# Hub.net
KiCad netlist of a schematic drawn in Altium Designer
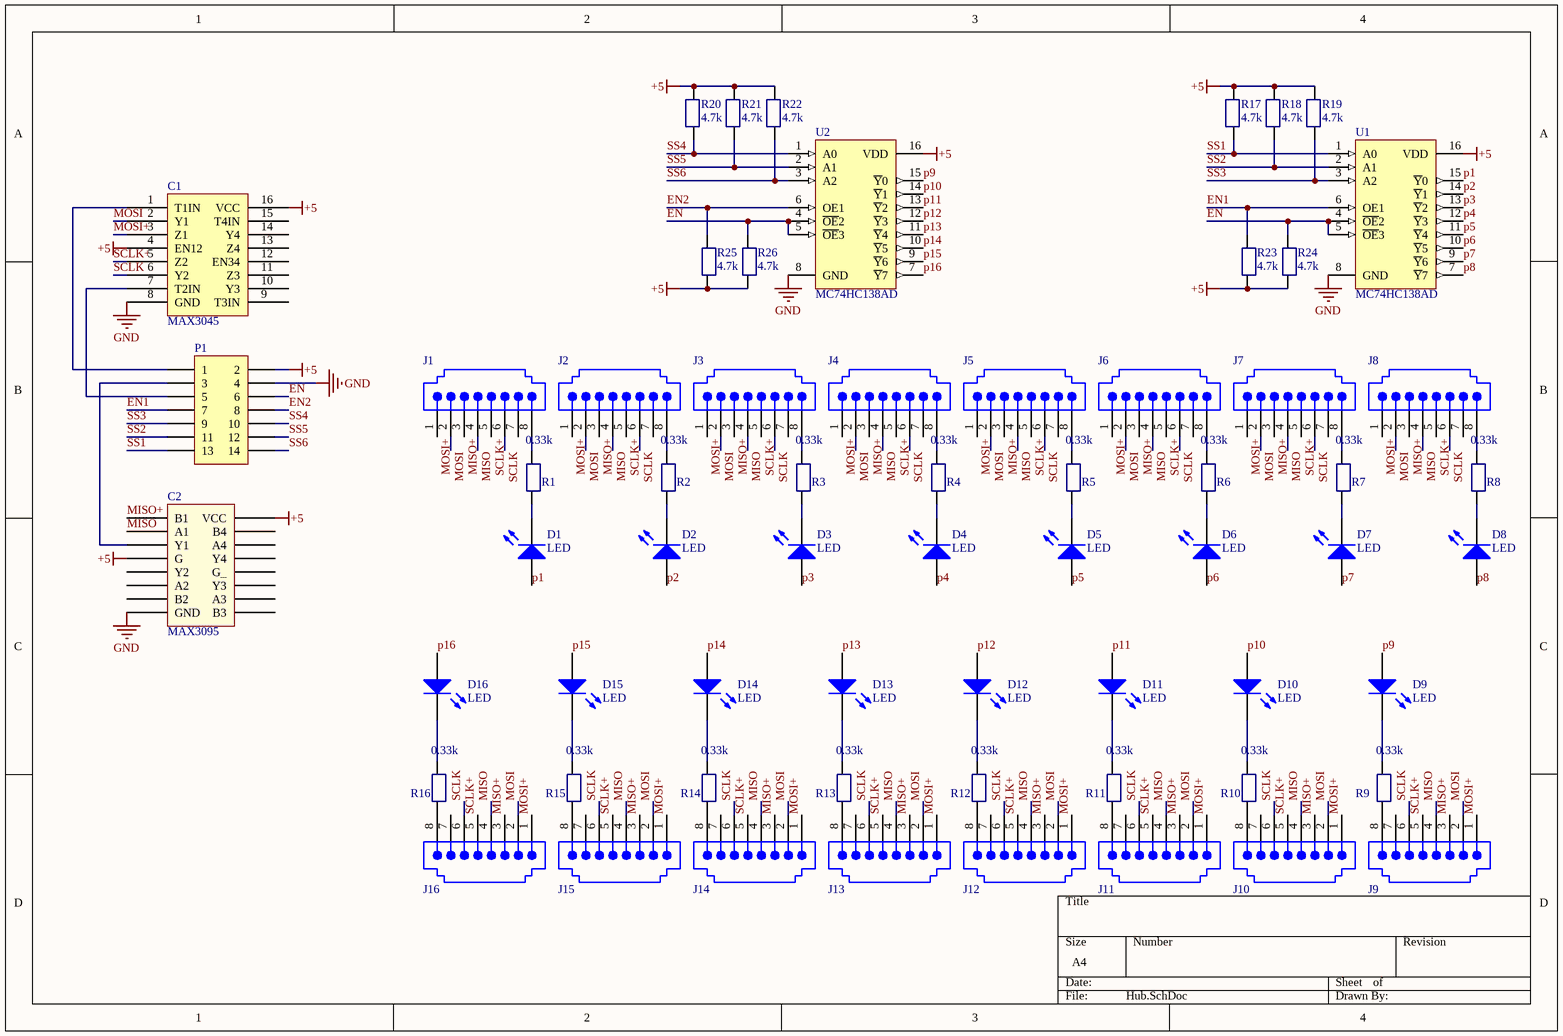
[diagram p0: Hub.SchDoc]

(export (version "E")
  (design (tool "Eeschema 10.0.6"))
  (components
    (comp (ref "C1") (value "MAX3045") (footprint "SOP16") (libsource (lib "DeersADLib") (part "MAX3045")))
    (comp (ref "C2") (value "MAX3095") (footprint "SOP16") (libsource (lib "DeersADLib") (part "MAX3095")))
    (comp (ref "D1")
      (value "LED")
      (footprint "3.5X2.8X1.9")
      (description "Typical BLUE SiC LED")
      (fields (field (name "PUBLISHER") "Altium Limited"))
      (libsource (lib "Miscellaneous Devices") (part "LED3"))
    )
    (comp (ref "D2")
      (value "LED")
      (footprint "3.5X2.8X1.9")
      (description "Typical BLUE SiC LED")
      (fields (field (name "PUBLISHER") "Altium Limited"))
      (libsource (lib "Miscellaneous Devices") (part "LED3"))
    )
    (comp (ref "D3")
      (value "LED")
      (footprint "3.5X2.8X1.9")
      (description "Typical BLUE SiC LED")
      (fields (field (name "PUBLISHER") "Altium Limited"))
      (libsource (lib "Miscellaneous Devices") (part "LED3"))
    )
    (comp (ref "D4")
      (value "LED")
      (footprint "3.5X2.8X1.9")
      (description "Typical BLUE SiC LED")
      (fields (field (name "PUBLISHER") "Altium Limited"))
      (libsource (lib "Miscellaneous Devices") (part "LED3"))
    )
    (comp (ref "D5")
      (value "LED")
      (footprint "3.5X2.8X1.9")
      (description "Typical BLUE SiC LED")
      (fields (field (name "PUBLISHER") "Altium Limited"))
      (libsource (lib "Miscellaneous Devices") (part "LED3"))
    )
    (comp (ref "D6")
      (value "LED")
      (footprint "3.5X2.8X1.9")
      (description "Typical BLUE SiC LED")
      (fields (field (name "PUBLISHER") "Altium Limited"))
      (libsource (lib "Miscellaneous Devices") (part "LED3"))
    )
    (comp (ref "D7")
      (value "LED")
      (footprint "3.5X2.8X1.9")
      (description "Typical BLUE SiC LED")
      (fields (field (name "PUBLISHER") "Altium Limited"))
      (libsource (lib "Miscellaneous Devices") (part "LED3"))
    )
    (comp (ref "D8")
      (value "LED")
      (footprint "3.5X2.8X1.9")
      (description "Typical BLUE SiC LED")
      (fields (field (name "PUBLISHER") "Altium Limited"))
      (libsource (lib "Miscellaneous Devices") (part "LED3"))
    )
    (comp (ref "D9")
      (value "LED")
      (footprint "3.5X2.8X1.9")
      (description "Typical BLUE SiC LED")
      (fields (field (name "PUBLISHER") "Altium Limited"))
      (libsource (lib "Miscellaneous Devices") (part "LED3"))
    )
    (comp (ref "D10")
      (value "LED")
      (footprint "3.5X2.8X1.9")
      (description "Typical BLUE SiC LED")
      (fields (field (name "PUBLISHER") "Altium Limited"))
      (libsource (lib "Miscellaneous Devices") (part "LED3"))
    )
    (comp (ref "D11")
      (value "LED")
      (footprint "3.5X2.8X1.9")
      (description "Typical BLUE SiC LED")
      (fields (field (name "PUBLISHER") "Altium Limited"))
      (libsource (lib "Miscellaneous Devices") (part "LED3"))
    )
    (comp (ref "D12")
      (value "LED")
      (footprint "3.5X2.8X1.9")
      (description "Typical BLUE SiC LED")
      (fields (field (name "PUBLISHER") "Altium Limited"))
      (libsource (lib "Miscellaneous Devices") (part "LED3"))
    )
    (comp (ref "D13")
      (value "LED")
      (footprint "3.5X2.8X1.9")
      (description "Typical BLUE SiC LED")
      (fields (field (name "PUBLISHER") "Altium Limited"))
      (libsource (lib "Miscellaneous Devices") (part "LED3"))
    )
    (comp (ref "D14")
      (value "LED")
      (footprint "3.5X2.8X1.9")
      (description "Typical BLUE SiC LED")
      (fields (field (name "PUBLISHER") "Altium Limited"))
      (libsource (lib "Miscellaneous Devices") (part "LED3"))
    )
    (comp (ref "D15")
      (value "LED")
      (footprint "3.5X2.8X1.9")
      (description "Typical BLUE SiC LED")
      (fields (field (name "PUBLISHER") "Altium Limited"))
      (libsource (lib "Miscellaneous Devices") (part "LED3"))
    )
    (comp (ref "D16")
      (value "LED")
      (footprint "3.5X2.8X1.9")
      (description "Typical BLUE SiC LED")
      (fields (field (name "PUBLISHER") "Altium Limited"))
      (libsource (lib "Miscellaneous Devices") (part "LED3"))
    )
    (comp (ref "J1")
      (value "15-43-6233")
      (footprint "15-43-6233")
      (description "Right Angle, Standard Profile, RJ45-Keyed, Flange Mount PCB Jack")
      (fields (field (name "PUBLISHER") "Altium Limited"))
      (libsource (lib "Molex Modular Jack Right Angle") (part "15-43-6233"))
    )
    (comp (ref "J2")
      (value "15-43-6233")
      (footprint "15-43-6233")
      (description "Right Angle, Standard Profile, RJ45-Keyed, Flange Mount PCB Jack")
      (fields (field (name "PUBLISHER") "Altium Limited"))
      (libsource (lib "Molex Modular Jack Right Angle") (part "15-43-6233"))
    )
    (comp (ref "J3")
      (value "15-43-6233")
      (footprint "15-43-6233")
      (description "Right Angle, Standard Profile, RJ45-Keyed, Flange Mount PCB Jack")
      (fields (field (name "PUBLISHER") "Altium Limited"))
      (libsource (lib "Molex Modular Jack Right Angle") (part "15-43-6233"))
    )
    (comp (ref "J4")
      (value "15-43-6233")
      (footprint "15-43-6233")
      (description "Right Angle, Standard Profile, RJ45-Keyed, Flange Mount PCB Jack")
      (fields (field (name "PUBLISHER") "Altium Limited"))
      (libsource (lib "Molex Modular Jack Right Angle") (part "15-43-6233"))
    )
    (comp (ref "J5")
      (value "15-43-6233")
      (footprint "15-43-6233")
      (description "Right Angle, Standard Profile, RJ45-Keyed, Flange Mount PCB Jack")
      (fields (field (name "PUBLISHER") "Altium Limited"))
      (libsource (lib "Molex Modular Jack Right Angle") (part "15-43-6233"))
    )
    (comp (ref "J6")
      (value "15-43-6233")
      (footprint "15-43-6233")
      (description "Right Angle, Standard Profile, RJ45-Keyed, Flange Mount PCB Jack")
      (fields (field (name "PUBLISHER") "Altium Limited"))
      (libsource (lib "Molex Modular Jack Right Angle") (part "15-43-6233"))
    )
    (comp (ref "J7")
      (value "15-43-6233")
      (footprint "15-43-6233")
      (description "Right Angle, Standard Profile, RJ45-Keyed, Flange Mount PCB Jack")
      (fields (field (name "PUBLISHER") "Altium Limited"))
      (libsource (lib "Molex Modular Jack Right Angle") (part "15-43-6233"))
    )
    (comp (ref "J8")
      (value "15-43-6233")
      (footprint "15-43-6233")
      (description "Right Angle, Standard Profile, RJ45-Keyed, Flange Mount PCB Jack")
      (fields (field (name "PUBLISHER") "Altium Limited"))
      (libsource (lib "Molex Modular Jack Right Angle") (part "15-43-6233"))
    )
    (comp (ref "J9")
      (value "15-43-6233")
      (footprint "15-43-6233")
      (description "Right Angle, Standard Profile, RJ45-Keyed, Flange Mount PCB Jack")
      (fields (field (name "PUBLISHER") "Altium Limited"))
      (libsource (lib "Molex Modular Jack Right Angle") (part "15-43-6233"))
    )
    (comp (ref "J10")
      (value "15-43-6233")
      (footprint "15-43-6233")
      (description "Right Angle, Standard Profile, RJ45-Keyed, Flange Mount PCB Jack")
      (fields (field (name "PUBLISHER") "Altium Limited"))
      (libsource (lib "Molex Modular Jack Right Angle") (part "15-43-6233"))
    )
    (comp (ref "J11")
      (value "15-43-6233")
      (footprint "15-43-6233")
      (description "Right Angle, Standard Profile, RJ45-Keyed, Flange Mount PCB Jack")
      (fields (field (name "PUBLISHER") "Altium Limited"))
      (libsource (lib "Molex Modular Jack Right Angle") (part "15-43-6233"))
    )
    (comp (ref "J12")
      (value "15-43-6233")
      (footprint "15-43-6233")
      (description "Right Angle, Standard Profile, RJ45-Keyed, Flange Mount PCB Jack")
      (fields (field (name "PUBLISHER") "Altium Limited"))
      (libsource (lib "Molex Modular Jack Right Angle") (part "15-43-6233"))
    )
    (comp (ref "J13")
      (value "15-43-6233")
      (footprint "15-43-6233")
      (description "Right Angle, Standard Profile, RJ45-Keyed, Flange Mount PCB Jack")
      (fields (field (name "PUBLISHER") "Altium Limited"))
      (libsource (lib "Molex Modular Jack Right Angle") (part "15-43-6233"))
    )
    (comp (ref "J14")
      (value "15-43-6233")
      (footprint "15-43-6233")
      (description "Right Angle, Standard Profile, RJ45-Keyed, Flange Mount PCB Jack")
      (fields (field (name "PUBLISHER") "Altium Limited"))
      (libsource (lib "Molex Modular Jack Right Angle") (part "15-43-6233"))
    )
    (comp (ref "J15")
      (value "15-43-6233")
      (footprint "15-43-6233")
      (description "Right Angle, Standard Profile, RJ45-Keyed, Flange Mount PCB Jack")
      (fields (field (name "PUBLISHER") "Altium Limited"))
      (libsource (lib "Molex Modular Jack Right Angle") (part "15-43-6233"))
    )
    (comp (ref "J16")
      (value "15-43-6233")
      (footprint "15-43-6233")
      (description "Right Angle, Standard Profile, RJ45-Keyed, Flange Mount PCB Jack")
      (fields (field (name "PUBLISHER") "Altium Limited"))
      (libsource (lib "Molex Modular Jack Right Angle") (part "15-43-6233"))
    )
    (comp (ref "P1")
      (value "Header 7X2")
      (footprint "HDR1X14")
      (description "Header, 7-Pin, Dual row")
      (fields (field (name "PUBLISHER") "Altium Limited"))
      (libsource (lib "Common Headers") (part "Header 7X2"))
    )
    (comp (ref "R1")
      (value "0.33k")
      (footprint "R0805")
      (libsource (lib "Common Device") (part "Resistance"))
    )
    (comp (ref "R2")
      (value "0.33k")
      (footprint "R0805")
      (libsource (lib "Common Device") (part "Resistance"))
    )
    (comp (ref "R3")
      (value "0.33k")
      (footprint "R0805")
      (libsource (lib "Common Device") (part "Resistance"))
    )
    (comp (ref "R4")
      (value "0.33k")
      (footprint "R0805")
      (libsource (lib "Common Device") (part "Resistance"))
    )
    (comp (ref "R5")
      (value "0.33k")
      (footprint "R0805")
      (libsource (lib "Common Device") (part "Resistance"))
    )
    (comp (ref "R6")
      (value "0.33k")
      (footprint "R0805")
      (libsource (lib "Common Device") (part "Resistance"))
    )
    (comp (ref "R7")
      (value "0.33k")
      (footprint "R0805")
      (libsource (lib "Common Device") (part "Resistance"))
    )
    (comp (ref "R8")
      (value "0.33k")
      (footprint "R0805")
      (libsource (lib "Common Device") (part "Resistance"))
    )
    (comp (ref "R9")
      (value "0.33k")
      (footprint "R0805")
      (libsource (lib "Common Device") (part "Resistance"))
    )
    (comp (ref "R10")
      (value "0.33k")
      (footprint "R0805")
      (libsource (lib "Common Device") (part "Resistance"))
    )
    (comp (ref "R11")
      (value "0.33k")
      (footprint "R0805")
      (libsource (lib "Common Device") (part "Resistance"))
    )
    (comp (ref "R12")
      (value "0.33k")
      (footprint "R0805")
      (libsource (lib "Common Device") (part "Resistance"))
    )
    (comp (ref "R13")
      (value "0.33k")
      (footprint "R0805")
      (libsource (lib "Common Device") (part "Resistance"))
    )
    (comp (ref "R14")
      (value "0.33k")
      (footprint "R0805")
      (libsource (lib "Common Device") (part "Resistance"))
    )
    (comp (ref "R15")
      (value "0.33k")
      (footprint "R0805")
      (libsource (lib "Common Device") (part "Resistance"))
    )
    (comp (ref "R16")
      (value "0.33k")
      (footprint "R0805")
      (libsource (lib "Common Device") (part "Resistance"))
    )
    (comp (ref "R17")
      (value "4.7k")
      (footprint "R0805")
      (libsource (lib "Common Device") (part "Resistance"))
    )
    (comp (ref "R18")
      (value "4.7k")
      (footprint "R0805")
      (libsource (lib "Common Device") (part "Resistance"))
    )
    (comp (ref "R19")
      (value "4.7k")
      (footprint "R0805")
      (libsource (lib "Common Device") (part "Resistance"))
    )
    (comp (ref "R20")
      (value "4.7k")
      (footprint "R0805")
      (libsource (lib "Common Device") (part "Resistance"))
    )
    (comp (ref "R21")
      (value "4.7k")
      (footprint "R0805")
      (libsource (lib "Common Device") (part "Resistance"))
    )
    (comp (ref "R22")
      (value "4.7k")
      (footprint "R0805")
      (libsource (lib "Common Device") (part "Resistance"))
    )
    (comp (ref "R23")
      (value "4.7k")
      (footprint "R0805")
      (libsource (lib "Common Device") (part "Resistance"))
    )
    (comp (ref "R24")
      (value "4.7k")
      (footprint "R0805")
      (libsource (lib "Common Device") (part "Resistance"))
    )
    (comp (ref "R25")
      (value "4.7k")
      (footprint "R0805")
      (libsource (lib "Common Device") (part "Resistance"))
    )
    (comp (ref "R26")
      (value "4.7k")
      (footprint "R0805")
      (libsource (lib "Common Device") (part "Resistance"))
    )
    (comp (ref "U1")
      (value "MC74HC138AD")
      (footprint "751B-03_L")
      (description "1-of-8 Decoder/Demultiplexer")
      (fields (field (name "PUBLISHER") "Altium Limited"))
      (libsource (lib "Motorola Logic Decoder Demux") (part "MC74HC138AD"))
    )
    (comp (ref "U2")
      (value "MC74HC138AD")
      (footprint "751B-03_L")
      (description "1-of-8 Decoder/Demultiplexer")
      (fields (field (name "PUBLISHER") "Altium Limited"))
      (libsource (lib "Motorola Logic Decoder Demux") (part "MC74HC138AD"))
    )
  )
  (nets
    (net (code "1") (name "+5") (class "Default")
      (node (ref "C1") (pin "16") (pinfunction "VCC_16") (pintype "passive"))
      (node (ref "C1") (pin "4") (pinfunction "EN12_4") (pintype "passive"))
      (node (ref "C2") (pin "16") (pinfunction "VCC_16") (pintype "passive"))
      (node (ref "C2") (pin "4") (pinfunction "G_4") (pintype "passive"))
      (node (ref "P1") (pin "2") (pinfunction "2_2") (pintype "passive"))
      (node (ref "R17") (pin "1") (pintype "passive"))
      (node (ref "R18") (pin "1") (pintype "passive"))
      (node (ref "R19") (pin "1") (pintype "passive"))
      (node (ref "R20") (pin "1") (pintype "passive"))
      (node (ref "R21") (pin "1") (pintype "passive"))
      (node (ref "R22") (pin "1") (pintype "passive"))
      (node (ref "R23") (pin "1") (pintype "passive"))
      (node (ref "R24") (pin "1") (pintype "passive"))
      (node (ref "R25") (pin "1") (pintype "passive"))
      (node (ref "R26") (pin "1") (pintype "passive"))
      (node (ref "U1") (pin "16") (pinfunction "VDD_16") (pintype "power_in"))
      (node (ref "U2") (pin "16") (pinfunction "VDD_16") (pintype "power_in"))
    )
    (net (code "2") (name "/EN") (class "Default")
      (node (ref "P1") (pin "6") (pinfunction "6_6") (pintype "passive"))
      (node (ref "R24") (pin "2") (pintype "passive"))
      (node (ref "R26") (pin "2") (pintype "passive"))
      (node (ref "U1") (pin "4") (pinfunction "~{OE}2_4") (pintype "input"))
      (node (ref "U1") (pin "5") (pinfunction "~{OE}3_5") (pintype "input"))
      (node (ref "U2") (pin "4") (pinfunction "~{OE}2_4") (pintype "input"))
      (node (ref "U2") (pin "5") (pinfunction "~{OE}3_5") (pintype "input"))
    )
    (net (code "3") (name "/EN1") (class "Default")
      (node (ref "P1") (pin "7") (pinfunction "7_7") (pintype "passive"))
      (node (ref "R23") (pin "2") (pintype "passive"))
      (node (ref "U1") (pin "6") (pinfunction "OE1_6") (pintype "input"))
    )
    (net (code "4") (name "/EN2") (class "Default")
      (node (ref "P1") (pin "8") (pinfunction "8_8") (pintype "passive"))
      (node (ref "R25") (pin "2") (pintype "passive"))
      (node (ref "U2") (pin "6") (pinfunction "OE1_6") (pintype "input"))
    )
    (net (code "5") (name "/MISO") (class "Default")
      (node (ref "C2") (pin "2") (pinfunction "A1_2") (pintype "passive"))
      (node (ref "J1") (pin "4") (pinfunction "4_4") (pintype "passive"))
      (node (ref "J10") (pin "4") (pinfunction "4_4") (pintype "passive"))
      (node (ref "J11") (pin "4") (pinfunction "4_4") (pintype "passive"))
      (node (ref "J12") (pin "4") (pinfunction "4_4") (pintype "passive"))
      (node (ref "J13") (pin "4") (pinfunction "4_4") (pintype "passive"))
      (node (ref "J14") (pin "4") (pinfunction "4_4") (pintype "passive"))
      (node (ref "J15") (pin "4") (pinfunction "4_4") (pintype "passive"))
      (node (ref "J16") (pin "4") (pinfunction "4_4") (pintype "passive"))
      (node (ref "J2") (pin "4") (pinfunction "4_4") (pintype "passive"))
      (node (ref "J3") (pin "4") (pinfunction "4_4") (pintype "passive"))
      (node (ref "J4") (pin "4") (pinfunction "4_4") (pintype "passive"))
      (node (ref "J5") (pin "4") (pinfunction "4_4") (pintype "passive"))
      (node (ref "J6") (pin "4") (pinfunction "4_4") (pintype "passive"))
      (node (ref "J7") (pin "4") (pinfunction "4_4") (pintype "passive"))
      (node (ref "J8") (pin "4") (pinfunction "4_4") (pintype "passive"))
      (node (ref "J9") (pin "4") (pinfunction "4_4") (pintype "passive"))
    )
    (net (code "6") (name "/MISO+") (class "Default")
      (node (ref "C2") (pin "1") (pinfunction "B1_1") (pintype "passive"))
      (node (ref "J1") (pin "3") (pinfunction "3_3") (pintype "passive"))
      (node (ref "J10") (pin "3") (pinfunction "3_3") (pintype "passive"))
      (node (ref "J11") (pin "3") (pinfunction "3_3") (pintype "passive"))
      (node (ref "J12") (pin "3") (pinfunction "3_3") (pintype "passive"))
      (node (ref "J13") (pin "3") (pinfunction "3_3") (pintype "passive"))
      (node (ref "J14") (pin "3") (pinfunction "3_3") (pintype "passive"))
      (node (ref "J15") (pin "3") (pinfunction "3_3") (pintype "passive"))
      (node (ref "J16") (pin "3") (pinfunction "3_3") (pintype "passive"))
      (node (ref "J2") (pin "3") (pinfunction "3_3") (pintype "passive"))
      (node (ref "J3") (pin "3") (pinfunction "3_3") (pintype "passive"))
      (node (ref "J4") (pin "3") (pinfunction "3_3") (pintype "passive"))
      (node (ref "J5") (pin "3") (pinfunction "3_3") (pintype "passive"))
      (node (ref "J6") (pin "3") (pinfunction "3_3") (pintype "passive"))
      (node (ref "J7") (pin "3") (pinfunction "3_3") (pintype "passive"))
      (node (ref "J8") (pin "3") (pinfunction "3_3") (pintype "passive"))
      (node (ref "J9") (pin "3") (pinfunction "3_3") (pintype "passive"))
    )
    (net (code "7") (name "/MOSI") (class "Default")
      (node (ref "C1") (pin "2") (pinfunction "Y1_2") (pintype "passive"))
      (node (ref "J1") (pin "2") (pinfunction "2_2") (pintype "passive"))
      (node (ref "J10") (pin "2") (pinfunction "2_2") (pintype "passive"))
      (node (ref "J11") (pin "2") (pinfunction "2_2") (pintype "passive"))
      (node (ref "J12") (pin "2") (pinfunction "2_2") (pintype "passive"))
      (node (ref "J13") (pin "2") (pinfunction "2_2") (pintype "passive"))
      (node (ref "J14") (pin "2") (pinfunction "2_2") (pintype "passive"))
      (node (ref "J15") (pin "2") (pinfunction "2_2") (pintype "passive"))
      (node (ref "J16") (pin "2") (pinfunction "2_2") (pintype "passive"))
      (node (ref "J2") (pin "2") (pinfunction "2_2") (pintype "passive"))
      (node (ref "J3") (pin "2") (pinfunction "2_2") (pintype "passive"))
      (node (ref "J4") (pin "2") (pinfunction "2_2") (pintype "passive"))
      (node (ref "J5") (pin "2") (pinfunction "2_2") (pintype "passive"))
      (node (ref "J6") (pin "2") (pinfunction "2_2") (pintype "passive"))
      (node (ref "J7") (pin "2") (pinfunction "2_2") (pintype "passive"))
      (node (ref "J8") (pin "2") (pinfunction "2_2") (pintype "passive"))
      (node (ref "J9") (pin "2") (pinfunction "2_2") (pintype "passive"))
    )
    (net (code "8") (name "/MOSI+") (class "Default")
      (node (ref "C1") (pin "3") (pinfunction "Z1_3") (pintype "passive"))
      (node (ref "J1") (pin "1") (pinfunction "1_1") (pintype "passive"))
      (node (ref "J10") (pin "1") (pinfunction "1_1") (pintype "passive"))
      (node (ref "J11") (pin "1") (pinfunction "1_1") (pintype "passive"))
      (node (ref "J12") (pin "1") (pinfunction "1_1") (pintype "passive"))
      (node (ref "J13") (pin "1") (pinfunction "1_1") (pintype "passive"))
      (node (ref "J14") (pin "1") (pinfunction "1_1") (pintype "passive"))
      (node (ref "J15") (pin "1") (pinfunction "1_1") (pintype "passive"))
      (node (ref "J16") (pin "1") (pinfunction "1_1") (pintype "passive"))
      (node (ref "J2") (pin "1") (pinfunction "1_1") (pintype "passive"))
      (node (ref "J3") (pin "1") (pinfunction "1_1") (pintype "passive"))
      (node (ref "J4") (pin "1") (pinfunction "1_1") (pintype "passive"))
      (node (ref "J5") (pin "1") (pinfunction "1_1") (pintype "passive"))
      (node (ref "J6") (pin "1") (pinfunction "1_1") (pintype "passive"))
      (node (ref "J7") (pin "1") (pinfunction "1_1") (pintype "passive"))
      (node (ref "J8") (pin "1") (pinfunction "1_1") (pintype "passive"))
      (node (ref "J9") (pin "1") (pinfunction "1_1") (pintype "passive"))
    )
    (net (code "9") (name "/SCLK") (class "Default")
      (node (ref "C1") (pin "6") (pinfunction "Y2_6") (pintype "passive"))
      (node (ref "J1") (pin "6") (pinfunction "6_6") (pintype "passive"))
      (node (ref "J10") (pin "6") (pinfunction "6_6") (pintype "passive"))
      (node (ref "J11") (pin "6") (pinfunction "6_6") (pintype "passive"))
      (node (ref "J12") (pin "6") (pinfunction "6_6") (pintype "passive"))
      (node (ref "J13") (pin "6") (pinfunction "6_6") (pintype "passive"))
      (node (ref "J14") (pin "6") (pinfunction "6_6") (pintype "passive"))
      (node (ref "J15") (pin "6") (pinfunction "6_6") (pintype "passive"))
      (node (ref "J16") (pin "6") (pinfunction "6_6") (pintype "passive"))
      (node (ref "J2") (pin "6") (pinfunction "6_6") (pintype "passive"))
      (node (ref "J3") (pin "6") (pinfunction "6_6") (pintype "passive"))
      (node (ref "J4") (pin "6") (pinfunction "6_6") (pintype "passive"))
      (node (ref "J5") (pin "6") (pinfunction "6_6") (pintype "passive"))
      (node (ref "J6") (pin "6") (pinfunction "6_6") (pintype "passive"))
      (node (ref "J7") (pin "6") (pinfunction "6_6") (pintype "passive"))
      (node (ref "J8") (pin "6") (pinfunction "6_6") (pintype "passive"))
      (node (ref "J9") (pin "6") (pinfunction "6_6") (pintype "passive"))
    )
    (net (code "10") (name "/SCLK+") (class "Default")
      (node (ref "C1") (pin "5") (pinfunction "Z2_5") (pintype "passive"))
      (node (ref "J1") (pin "5") (pinfunction "5_5") (pintype "passive"))
      (node (ref "J10") (pin "5") (pinfunction "5_5") (pintype "passive"))
      (node (ref "J11") (pin "5") (pinfunction "5_5") (pintype "passive"))
      (node (ref "J12") (pin "5") (pinfunction "5_5") (pintype "passive"))
      (node (ref "J13") (pin "5") (pinfunction "5_5") (pintype "passive"))
      (node (ref "J14") (pin "5") (pinfunction "5_5") (pintype "passive"))
      (node (ref "J15") (pin "5") (pinfunction "5_5") (pintype "passive"))
      (node (ref "J16") (pin "5") (pinfunction "5_5") (pintype "passive"))
      (node (ref "J2") (pin "5") (pinfunction "5_5") (pintype "passive"))
      (node (ref "J3") (pin "5") (pinfunction "5_5") (pintype "passive"))
      (node (ref "J4") (pin "5") (pinfunction "5_5") (pintype "passive"))
      (node (ref "J5") (pin "5") (pinfunction "5_5") (pintype "passive"))
      (node (ref "J6") (pin "5") (pinfunction "5_5") (pintype "passive"))
      (node (ref "J7") (pin "5") (pinfunction "5_5") (pintype "passive"))
      (node (ref "J8") (pin "5") (pinfunction "5_5") (pintype "passive"))
      (node (ref "J9") (pin "5") (pinfunction "5_5") (pintype "passive"))
    )
    (net (code "11") (name "/SS1") (class "Default")
      (node (ref "P1") (pin "13") (pinfunction "13_13") (pintype "passive"))
      (node (ref "R17") (pin "2") (pintype "passive"))
      (node (ref "U1") (pin "1") (pinfunction "A0_1") (pintype "input"))
    )
    (net (code "12") (name "/SS2") (class "Default")
      (node (ref "P1") (pin "11") (pinfunction "11_11") (pintype "passive"))
      (node (ref "R18") (pin "2") (pintype "passive"))
      (node (ref "U1") (pin "2") (pinfunction "A1_2") (pintype "input"))
    )
    (net (code "13") (name "/SS3") (class "Default")
      (node (ref "P1") (pin "9") (pinfunction "9_9") (pintype "passive"))
      (node (ref "R19") (pin "2") (pintype "passive"))
      (node (ref "U1") (pin "3") (pinfunction "A2_3") (pintype "input"))
    )
    (net (code "14") (name "/SS4") (class "Default")
      (node (ref "P1") (pin "10") (pinfunction "10_10") (pintype "passive"))
      (node (ref "R20") (pin "2") (pintype "passive"))
      (node (ref "U2") (pin "1") (pinfunction "A0_1") (pintype "input"))
    )
    (net (code "15") (name "/SS5") (class "Default")
      (node (ref "P1") (pin "12") (pinfunction "12_12") (pintype "passive"))
      (node (ref "R21") (pin "2") (pintype "passive"))
      (node (ref "U2") (pin "2") (pinfunction "A1_2") (pintype "input"))
    )
    (net (code "16") (name "/SS6") (class "Default")
      (node (ref "P1") (pin "14") (pinfunction "14_14") (pintype "passive"))
      (node (ref "R22") (pin "2") (pintype "passive"))
      (node (ref "U2") (pin "3") (pinfunction "A2_3") (pintype "input"))
    )
    (net (code "17") (name "/p1") (class "Default")
      (node (ref "D1") (pin "1") (pinfunction "A_1") (pintype "passive"))
      (node (ref "U1") (pin "15") (pinfunction "~{Y}0_15") (pintype "output"))
    )
    (net (code "18") (name "/p2") (class "Default")
      (node (ref "D2") (pin "1") (pinfunction "A_1") (pintype "passive"))
      (node (ref "U1") (pin "14") (pinfunction "~{Y}1_14") (pintype "output"))
    )
    (net (code "19") (name "/p3") (class "Default")
      (node (ref "D3") (pin "1") (pinfunction "A_1") (pintype "passive"))
      (node (ref "U1") (pin "13") (pinfunction "~{Y}2_13") (pintype "output"))
    )
    (net (code "20") (name "/p4") (class "Default")
      (node (ref "D4") (pin "1") (pinfunction "A_1") (pintype "passive"))
      (node (ref "U1") (pin "12") (pinfunction "~{Y}3_12") (pintype "output"))
    )
    (net (code "21") (name "/p5") (class "Default")
      (node (ref "D5") (pin "1") (pinfunction "A_1") (pintype "passive"))
      (node (ref "U1") (pin "11") (pinfunction "~{Y}4_11") (pintype "output"))
    )
    (net (code "22") (name "/p6") (class "Default")
      (node (ref "D6") (pin "1") (pinfunction "A_1") (pintype "passive"))
      (node (ref "U1") (pin "10") (pinfunction "~{Y}5_10") (pintype "output"))
    )
    (net (code "23") (name "/p7") (class "Default")
      (node (ref "D7") (pin "1") (pinfunction "A_1") (pintype "passive"))
      (node (ref "U1") (pin "9") (pinfunction "~{Y}6_9") (pintype "output"))
    )
    (net (code "24") (name "/p8") (class "Default")
      (node (ref "D8") (pin "1") (pinfunction "A_1") (pintype "passive"))
      (node (ref "U1") (pin "7") (pinfunction "~{Y}7_7") (pintype "output"))
    )
    (net (code "25") (name "/p9") (class "Default")
      (node (ref "D9") (pin "1") (pinfunction "A_1") (pintype "passive"))
      (node (ref "U2") (pin "15") (pinfunction "~{Y}0_15") (pintype "output"))
    )
    (net (code "26") (name "/p10") (class "Default")
      (node (ref "D10") (pin "1") (pinfunction "A_1") (pintype "passive"))
      (node (ref "U2") (pin "14") (pinfunction "~{Y}1_14") (pintype "output"))
    )
    (net (code "27") (name "/p11") (class "Default")
      (node (ref "D11") (pin "1") (pinfunction "A_1") (pintype "passive"))
      (node (ref "U2") (pin "13") (pinfunction "~{Y}2_13") (pintype "output"))
    )
    (net (code "28") (name "/p12") (class "Default")
      (node (ref "D12") (pin "1") (pinfunction "A_1") (pintype "passive"))
      (node (ref "U2") (pin "12") (pinfunction "~{Y}3_12") (pintype "output"))
    )
    (net (code "29") (name "/p13") (class "Default")
      (node (ref "D13") (pin "1") (pinfunction "A_1") (pintype "passive"))
      (node (ref "U2") (pin "11") (pinfunction "~{Y}4_11") (pintype "output"))
    )
    (net (code "30") (name "/p14") (class "Default")
      (node (ref "D14") (pin "1") (pinfunction "A_1") (pintype "passive"))
      (node (ref "U2") (pin "10") (pinfunction "~{Y}5_10") (pintype "output"))
    )
    (net (code "31") (name "/p15") (class "Default")
      (node (ref "D15") (pin "1") (pinfunction "A_1") (pintype "passive"))
      (node (ref "U2") (pin "9") (pinfunction "~{Y}6_9") (pintype "output"))
    )
    (net (code "32") (name "/p16") (class "Default")
      (node (ref "D16") (pin "1") (pinfunction "A_1") (pintype "passive"))
      (node (ref "U2") (pin "7") (pinfunction "~{Y}7_7") (pintype "output"))
    )
    (net (code "33") (name "GND") (class "Default")
      (node (ref "C1") (pin "8") (pinfunction "GND_8") (pintype "passive"))
      (node (ref "C2") (pin "8") (pinfunction "GND_8") (pintype "passive"))
      (node (ref "P1") (pin "4") (pinfunction "4_4") (pintype "passive"))
      (node (ref "U1") (pin "8") (pinfunction "GND_8") (pintype "power_in"))
      (node (ref "U2") (pin "8") (pinfunction "GND_8") (pintype "power_in"))
    )
    (net (code "34") (name "Net-(C1-T1IN)") (class "Default")
      (node (ref "C1") (pin "1") (pinfunction "T1IN_1") (pintype "passive"))
      (node (ref "P1") (pin "1") (pinfunction "1_1") (pintype "passive"))
    )
    (net (code "35") (name "Net-(C1-T2IN)") (class "Default")
      (node (ref "C1") (pin "7") (pinfunction "T2IN_7") (pintype "passive"))
      (node (ref "P1") (pin "5") (pinfunction "5_5") (pintype "passive"))
    )
    (net (code "36") (name "Net-(C2-Y1)") (class "Default")
      (node (ref "C2") (pin "3") (pinfunction "Y1_3") (pintype "passive"))
      (node (ref "P1") (pin "3") (pinfunction "3_3") (pintype "passive"))
    )
    (net (code "37") (name "Net-(D1-K)") (class "Default")
      (node (ref "D1") (pin "2") (pinfunction "K_2") (pintype "passive"))
      (node (ref "R1") (pin "1") (pintype "passive"))
    )
    (net (code "38") (name "Net-(D2-K)") (class "Default")
      (node (ref "D2") (pin "2") (pinfunction "K_2") (pintype "passive"))
      (node (ref "R2") (pin "1") (pintype "passive"))
    )
    (net (code "39") (name "Net-(D3-K)") (class "Default")
      (node (ref "D3") (pin "2") (pinfunction "K_2") (pintype "passive"))
      (node (ref "R3") (pin "1") (pintype "passive"))
    )
    (net (code "40") (name "Net-(D4-K)") (class "Default")
      (node (ref "D4") (pin "2") (pinfunction "K_2") (pintype "passive"))
      (node (ref "R4") (pin "1") (pintype "passive"))
    )
    (net (code "41") (name "Net-(D5-K)") (class "Default")
      (node (ref "D5") (pin "2") (pinfunction "K_2") (pintype "passive"))
      (node (ref "R5") (pin "1") (pintype "passive"))
    )
    (net (code "42") (name "Net-(D6-K)") (class "Default")
      (node (ref "D6") (pin "2") (pinfunction "K_2") (pintype "passive"))
      (node (ref "R6") (pin "1") (pintype "passive"))
    )
    (net (code "43") (name "Net-(D7-K)") (class "Default")
      (node (ref "D7") (pin "2") (pinfunction "K_2") (pintype "passive"))
      (node (ref "R7") (pin "1") (pintype "passive"))
    )
    (net (code "44") (name "Net-(D8-K)") (class "Default")
      (node (ref "D8") (pin "2") (pinfunction "K_2") (pintype "passive"))
      (node (ref "R8") (pin "1") (pintype "passive"))
    )
    (net (code "45") (name "Net-(D9-K)") (class "Default")
      (node (ref "D9") (pin "2") (pinfunction "K_2") (pintype "passive"))
      (node (ref "R9") (pin "2") (pintype "passive"))
    )
    (net (code "46") (name "Net-(D10-K)") (class "Default")
      (node (ref "D10") (pin "2") (pinfunction "K_2") (pintype "passive"))
      (node (ref "R10") (pin "2") (pintype "passive"))
    )
    (net (code "47") (name "Net-(D11-K)") (class "Default")
      (node (ref "D11") (pin "2") (pinfunction "K_2") (pintype "passive"))
      (node (ref "R11") (pin "2") (pintype "passive"))
    )
    (net (code "48") (name "Net-(D12-K)") (class "Default")
      (node (ref "D12") (pin "2") (pinfunction "K_2") (pintype "passive"))
      (node (ref "R12") (pin "2") (pintype "passive"))
    )
    (net (code "49") (name "Net-(D13-K)") (class "Default")
      (node (ref "D13") (pin "2") (pinfunction "K_2") (pintype "passive"))
      (node (ref "R13") (pin "2") (pintype "passive"))
    )
    (net (code "50") (name "Net-(D14-K)") (class "Default")
      (node (ref "D14") (pin "2") (pinfunction "K_2") (pintype "passive"))
      (node (ref "R14") (pin "2") (pintype "passive"))
    )
    (net (code "51") (name "Net-(D15-K)") (class "Default")
      (node (ref "D15") (pin "2") (pinfunction "K_2") (pintype "passive"))
      (node (ref "R15") (pin "2") (pintype "passive"))
    )
    (net (code "52") (name "Net-(D16-K)") (class "Default")
      (node (ref "D16") (pin "2") (pinfunction "K_2") (pintype "passive"))
      (node (ref "R16") (pin "2") (pintype "passive"))
    )
    (net (code "53") (name "Net-(J1-Pad8)") (class "Default")
      (node (ref "J1") (pin "8") (pinfunction "8_8") (pintype "passive"))
      (node (ref "R1") (pin "2") (pintype "passive"))
    )
    (net (code "54") (name "Net-(J2-Pad8)") (class "Default")
      (node (ref "J2") (pin "8") (pinfunction "8_8") (pintype "passive"))
      (node (ref "R2") (pin "2") (pintype "passive"))
    )
    (net (code "55") (name "Net-(J3-Pad8)") (class "Default")
      (node (ref "J3") (pin "8") (pinfunction "8_8") (pintype "passive"))
      (node (ref "R3") (pin "2") (pintype "passive"))
    )
    (net (code "56") (name "Net-(J4-Pad8)") (class "Default")
      (node (ref "J4") (pin "8") (pinfunction "8_8") (pintype "passive"))
      (node (ref "R4") (pin "2") (pintype "passive"))
    )
    (net (code "57") (name "Net-(J5-Pad8)") (class "Default")
      (node (ref "J5") (pin "8") (pinfunction "8_8") (pintype "passive"))
      (node (ref "R5") (pin "2") (pintype "passive"))
    )
    (net (code "58") (name "Net-(J6-Pad8)") (class "Default")
      (node (ref "J6") (pin "8") (pinfunction "8_8") (pintype "passive"))
      (node (ref "R6") (pin "2") (pintype "passive"))
    )
    (net (code "59") (name "Net-(J7-Pad8)") (class "Default")
      (node (ref "J7") (pin "8") (pinfunction "8_8") (pintype "passive"))
      (node (ref "R7") (pin "2") (pintype "passive"))
    )
    (net (code "60") (name "Net-(J8-Pad8)") (class "Default")
      (node (ref "J8") (pin "8") (pinfunction "8_8") (pintype "passive"))
      (node (ref "R8") (pin "2") (pintype "passive"))
    )
    (net (code "61") (name "Net-(J9-Pad8)") (class "Default")
      (node (ref "J9") (pin "8") (pinfunction "8_8") (pintype "passive"))
      (node (ref "R9") (pin "1") (pintype "passive"))
    )
    (net (code "62") (name "Net-(J10-Pad8)") (class "Default")
      (node (ref "J10") (pin "8") (pinfunction "8_8") (pintype "passive"))
      (node (ref "R10") (pin "1") (pintype "passive"))
    )
    (net (code "63") (name "Net-(J11-Pad8)") (class "Default")
      (node (ref "J11") (pin "8") (pinfunction "8_8") (pintype "passive"))
      (node (ref "R11") (pin "1") (pintype "passive"))
    )
    (net (code "64") (name "Net-(J12-Pad8)") (class "Default")
      (node (ref "J12") (pin "8") (pinfunction "8_8") (pintype "passive"))
      (node (ref "R12") (pin "1") (pintype "passive"))
    )
    (net (code "65") (name "Net-(J13-Pad8)") (class "Default")
      (node (ref "J13") (pin "8") (pinfunction "8_8") (pintype "passive"))
      (node (ref "R13") (pin "1") (pintype "passive"))
    )
    (net (code "66") (name "Net-(J14-Pad8)") (class "Default")
      (node (ref "J14") (pin "8") (pinfunction "8_8") (pintype "passive"))
      (node (ref "R14") (pin "1") (pintype "passive"))
    )
    (net (code "67") (name "Net-(J15-Pad8)") (class "Default")
      (node (ref "J15") (pin "8") (pinfunction "8_8") (pintype "passive"))
      (node (ref "R15") (pin "1") (pintype "passive"))
    )
    (net (code "68") (name "Net-(J16-Pad8)") (class "Default")
      (node (ref "J16") (pin "8") (pinfunction "8_8") (pintype "passive"))
      (node (ref "R16") (pin "1") (pintype "passive"))
    )
    (net (code "69") (name "unconnected-(C1-EN34-Pad12)") (class "Default")
      (node (ref "C1") (pin "12") (pinfunction "EN34_12") (pintype "passive"))
    )
    (net (code "70") (name "unconnected-(C1-T3IN-Pad9)") (class "Default")
      (node (ref "C1") (pin "9") (pinfunction "T3IN_9") (pintype "passive"))
    )
    (net (code "71") (name "unconnected-(C1-T4IN-Pad15)") (class "Default")
      (node (ref "C1") (pin "15") (pinfunction "T4IN_15") (pintype "passive"))
    )
    (net (code "72") (name "unconnected-(C1-Y3-Pad10)") (class "Default")
      (node (ref "C1") (pin "10") (pinfunction "Y3_10") (pintype "passive"))
    )
    (net (code "73") (name "unconnected-(C1-Y4-Pad14)") (class "Default")
      (node (ref "C1") (pin "14") (pinfunction "Y4_14") (pintype "passive"))
    )
    (net (code "74") (name "unconnected-(C1-Z3-Pad11)") (class "Default")
      (node (ref "C1") (pin "11") (pinfunction "Z3_11") (pintype "passive"))
    )
    (net (code "75") (name "unconnected-(C1-Z4-Pad13)") (class "Default")
      (node (ref "C1") (pin "13") (pinfunction "Z4_13") (pintype "passive"))
    )
    (net (code "76") (name "unconnected-(C2-A2-Pad6)") (class "Default")
      (node (ref "C2") (pin "6") (pinfunction "A2_6") (pintype "passive"))
    )
    (net (code "77") (name "unconnected-(C2-A3-Pad10)") (class "Default")
      (node (ref "C2") (pin "10") (pinfunction "A3_10") (pintype "passive"))
    )
    (net (code "78") (name "unconnected-(C2-A4-Pad14)") (class "Default")
      (node (ref "C2") (pin "14") (pinfunction "A4_14") (pintype "passive"))
    )
    (net (code "79") (name "unconnected-(C2-B2-Pad7)") (class "Default")
      (node (ref "C2") (pin "7") (pinfunction "B2_7") (pintype "passive"))
    )
    (net (code "80") (name "unconnected-(C2-B3-Pad9)") (class "Default")
      (node (ref "C2") (pin "9") (pinfunction "B3_9") (pintype "passive"))
    )
    (net (code "81") (name "unconnected-(C2-B4-Pad15)") (class "Default")
      (node (ref "C2") (pin "15") (pinfunction "B4_15") (pintype "passive"))
    )
    (net (code "82") (name "unconnected-(C2-G_-Pad12)") (class "Default")
      (node (ref "C2") (pin "12") (pinfunction "G__12") (pintype "passive"))
    )
    (net (code "83") (name "unconnected-(C2-Y2-Pad5)") (class "Default")
      (node (ref "C2") (pin "5") (pinfunction "Y2_5") (pintype "passive"))
    )
    (net (code "84") (name "unconnected-(C2-Y3-Pad11)") (class "Default")
      (node (ref "C2") (pin "11") (pinfunction "Y3_11") (pintype "passive"))
    )
    (net (code "85") (name "unconnected-(C2-Y4-Pad13)") (class "Default")
      (node (ref "C2") (pin "13") (pinfunction "Y4_13") (pintype "passive"))
    )
    (net (code "86") (name "unconnected-(J1-Pad7)") (class "Default")
      (node (ref "J1") (pin "7") (pinfunction "7_7") (pintype "passive"))
    )
    (net (code "87") (name "unconnected-(J2-Pad7)") (class "Default")
      (node (ref "J2") (pin "7") (pinfunction "7_7") (pintype "passive"))
    )
    (net (code "88") (name "unconnected-(J3-Pad7)") (class "Default")
      (node (ref "J3") (pin "7") (pinfunction "7_7") (pintype "passive"))
    )
    (net (code "89") (name "unconnected-(J4-Pad7)") (class "Default")
      (node (ref "J4") (pin "7") (pinfunction "7_7") (pintype "passive"))
    )
    (net (code "90") (name "unconnected-(J5-Pad7)") (class "Default")
      (node (ref "J5") (pin "7") (pinfunction "7_7") (pintype "passive"))
    )
    (net (code "91") (name "unconnected-(J6-Pad7)") (class "Default")
      (node (ref "J6") (pin "7") (pinfunction "7_7") (pintype "passive"))
    )
    (net (code "92") (name "unconnected-(J7-Pad7)") (class "Default")
      (node (ref "J7") (pin "7") (pinfunction "7_7") (pintype "passive"))
    )
    (net (code "93") (name "unconnected-(J8-Pad7)") (class "Default")
      (node (ref "J8") (pin "7") (pinfunction "7_7") (pintype "passive"))
    )
    (net (code "94") (name "unconnected-(J9-Pad7)") (class "Default")
      (node (ref "J9") (pin "7") (pinfunction "7_7") (pintype "passive"))
    )
    (net (code "95") (name "unconnected-(J10-Pad7)") (class "Default")
      (node (ref "J10") (pin "7") (pinfunction "7_7") (pintype "passive"))
    )
    (net (code "96") (name "unconnected-(J11-Pad7)") (class "Default")
      (node (ref "J11") (pin "7") (pinfunction "7_7") (pintype "passive"))
    )
    (net (code "97") (name "unconnected-(J12-Pad7)") (class "Default")
      (node (ref "J12") (pin "7") (pinfunction "7_7") (pintype "passive"))
    )
    (net (code "98") (name "unconnected-(J13-Pad7)") (class "Default")
      (node (ref "J13") (pin "7") (pinfunction "7_7") (pintype "passive"))
    )
    (net (code "99") (name "unconnected-(J14-Pad7)") (class "Default")
      (node (ref "J14") (pin "7") (pinfunction "7_7") (pintype "passive"))
    )
    (net (code "100") (name "unconnected-(J15-Pad7)") (class "Default")
      (node (ref "J15") (pin "7") (pinfunction "7_7") (pintype "passive"))
    )
    (net (code "101") (name "unconnected-(J16-Pad7)") (class "Default")
      (node (ref "J16") (pin "7") (pinfunction "7_7") (pintype "passive"))
    )
  )
)
